# Relay.net
KiCad netlist of a schematic drawn in Altium Designer
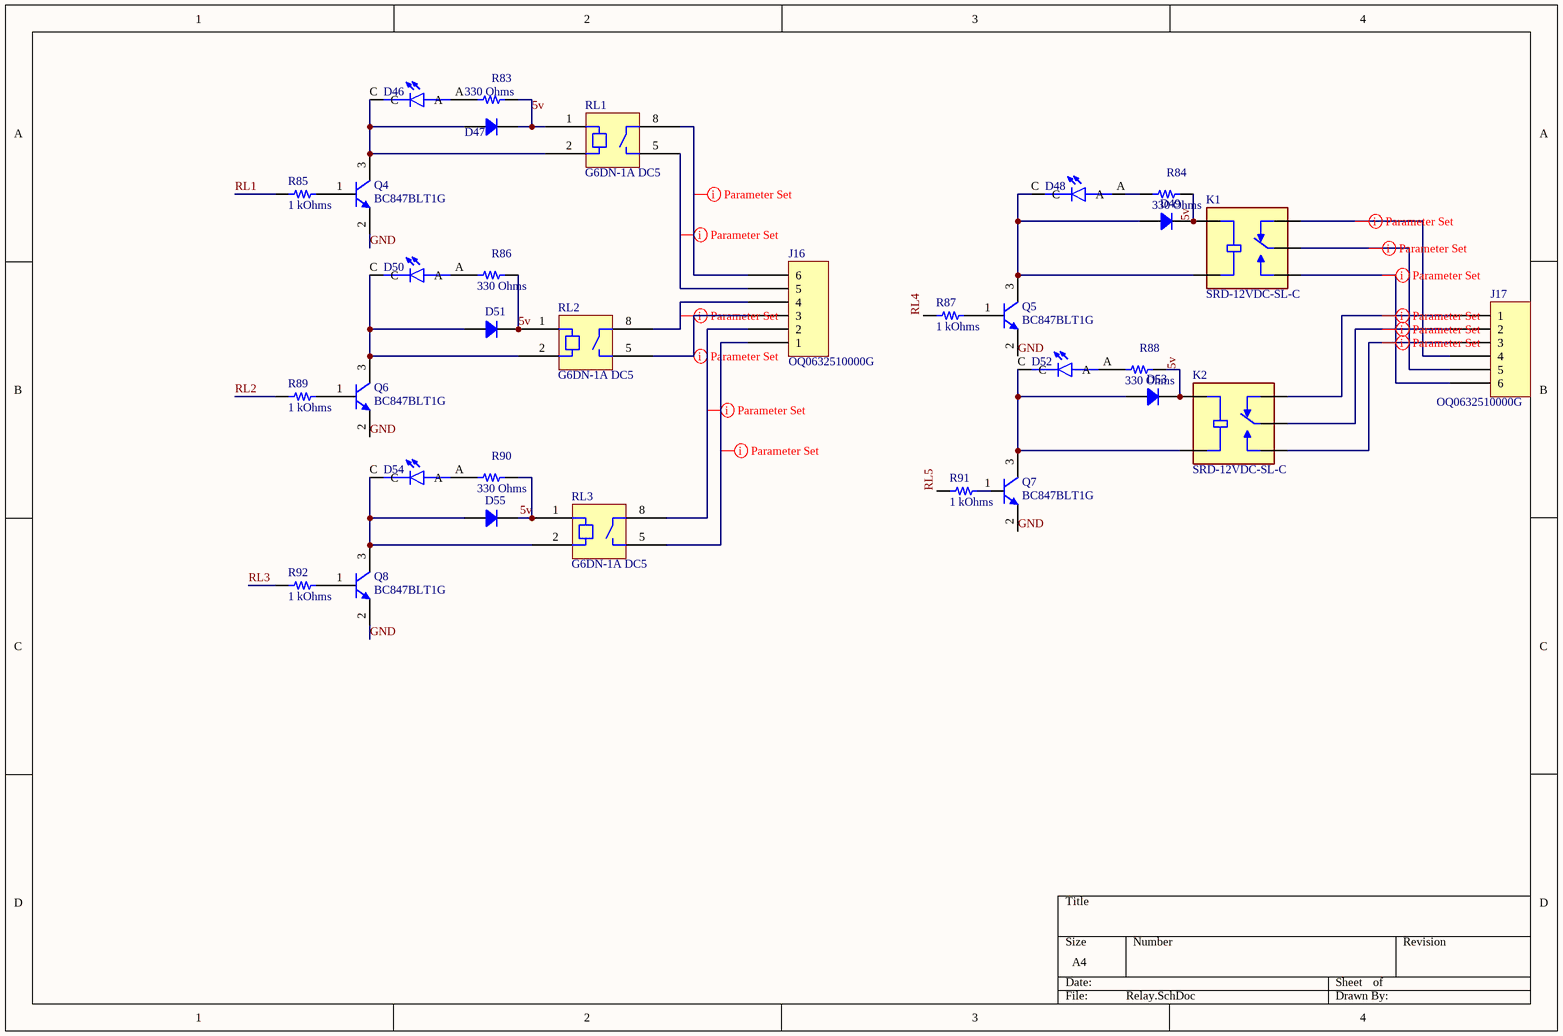
[diagram p0: Relay.SchDoc]

(export (version "E")
  (design (tool "Eeschema 10.0.6"))
  (components
    (comp (ref "D46")
      (value "597-3305-607F")
      (footprint "LEDC2012X70N")
      (description "LED Uni-Color Green 4-Pin Chip 0805 T/R")
      (libsource (lib "597-3305-607F") (part "597-3305-607F"))
    )
    (comp (ref "D47")
      (value "CGRA4007-G")
      (footprint "DO214AC SMA")
      (description "DIODE GEN PURP 1KV 1A DO214AC")
      (fields (field (name "MANUFACTURER") "Comchip Technology"))
      (libsource (lib "Celestial Altium Library - altium_library") (part "Diode"))
    )
    (comp (ref "D48")
      (value "597-3305-607F")
      (footprint "LEDC2012X70N")
      (description "LED Uni-Color Green 4-Pin Chip 0805 T/R")
      (libsource (lib "597-3305-607F") (part "597-3305-607F"))
    )
    (comp (ref "D49")
      (value "CGRA4007-G")
      (footprint "DO214AC SMA")
      (description "DIODE GEN PURP 1KV 1A DO214AC")
      (fields (field (name "MANUFACTURER") "Comchip Technology"))
      (libsource (lib "Celestial Altium Library - altium_library") (part "Diode"))
    )
    (comp (ref "D50")
      (value "597-3305-607F")
      (footprint "LEDC2012X70N")
      (description "LED Uni-Color Green 4-Pin Chip 0805 T/R")
      (libsource (lib "597-3305-607F") (part "597-3305-607F"))
    )
    (comp (ref "D51")
      (value "CGRA4007-G")
      (footprint "DO214AC SMA")
      (description "DIODE GEN PURP 1KV 1A DO214AC")
      (fields (field (name "MANUFACTURER") "Comchip Technology"))
      (libsource (lib "Celestial Altium Library - altium_library") (part "Diode"))
    )
    (comp (ref "D52")
      (value "597-3305-607F")
      (footprint "LEDC2012X70N")
      (description "LED Uni-Color Green 4-Pin Chip 0805 T/R")
      (libsource (lib "597-3305-607F") (part "597-3305-607F"))
    )
    (comp (ref "D53")
      (value "CGRA4007-G")
      (footprint "DO214AC SMA")
      (description "DIODE GEN PURP 1KV 1A DO214AC")
      (fields (field (name "MANUFACTURER") "Comchip Technology"))
      (libsource (lib "Celestial Altium Library - altium_library") (part "Diode"))
    )
    (comp (ref "D54")
      (value "597-3305-607F")
      (footprint "LEDC2012X70N")
      (description "LED Uni-Color Green 4-Pin Chip 0805 T/R")
      (libsource (lib "597-3305-607F") (part "597-3305-607F"))
    )
    (comp (ref "D55")
      (value "CGRA4007-G")
      (footprint "DO214AC SMA")
      (description "DIODE GEN PURP 1KV 1A DO214AC")
      (fields (field (name "MANUFACTURER") "Comchip Technology"))
      (libsource (lib "Celestial Altium Library - altium_library") (part "Diode"))
    )
    (comp (ref "J16")
      (value "OQ0632510000G")
      (footprint "FCI 06-381-6PIN")
      (description "TERM BLOCK HDR 6POS 90DEG 3.81MM")
      (fields (field (name "MANUFACTURER") "Amphenol Anytek"))
      (libsource (lib "") (part "6 Pin_1"))
    )
    (comp (ref "J17")
      (value "OQ0632510000G")
      (footprint "FCI 06-381-6PIN")
      (description "TERM BLOCK HDR 6POS 90DEG 3.81MM")
      (fields (field (name "MANUFACTURER") "Amphenol Anytek"))
      (libsource (lib "Celestial Altium Library - altium_library") (part "6 Pin"))
    )
    (comp (ref "K1")
      (value "SRD-12VDC-SL-C")
      (footprint "RELAY_SRD-12VDC-SL-C")
      (description "General Purpose Non Latching 12VDC SPDT Through Hole Relays RoHS")
      (fields (field (name "MF") "Songle Relay"))
      (libsource (lib "SRD-12VDC-SL-C") (part "SRD-12VDC-SL-C"))
    )
    (comp (ref "K2")
      (value "SRD-12VDC-SL-C")
      (footprint "RELAY_SRD-12VDC-SL-C")
      (description "General Purpose Non Latching 12VDC SPDT Through Hole Relays RoHS")
      (fields (field (name "MF") "Songle Relay"))
      (libsource (lib "SRD-12VDC-SL-C") (part "SRD-12VDC-SL-C"))
    )
    (comp (ref "Q4")
      (value "BC847BLT1G")
      (footprint "ON SEMI SOT-23-3")
      (description "TRANS NPN 45V 0.1A SOT23")
      (fields (field (name "MANUFACTURER") "ON Semiconductor"))
      (libsource (lib "Celestial Altium Library - altium_library") (part "ON SEMI NPN SOT-23-3"))
    )
    (comp (ref "Q5")
      (value "BC847BLT1G")
      (footprint "ON SEMI SOT-23-3")
      (description "TRANS NPN 45V 0.1A SOT23")
      (fields (field (name "MANUFACTURER") "ON Semiconductor"))
      (libsource (lib "Celestial Altium Library - altium_library") (part "ON SEMI NPN SOT-23-3"))
    )
    (comp (ref "Q6")
      (value "BC847BLT1G")
      (footprint "ON SEMI SOT-23-3")
      (description "TRANS NPN 45V 0.1A SOT23")
      (fields (field (name "MANUFACTURER") "ON Semiconductor"))
      (libsource (lib "Celestial Altium Library - altium_library") (part "ON SEMI NPN SOT-23-3"))
    )
    (comp (ref "Q7")
      (value "BC847BLT1G")
      (footprint "ON SEMI SOT-23-3")
      (description "TRANS NPN 45V 0.1A SOT23")
      (fields (field (name "MANUFACTURER") "ON Semiconductor"))
      (libsource (lib "Celestial Altium Library - altium_library") (part "ON SEMI NPN SOT-23-3"))
    )
    (comp (ref "Q8")
      (value "BC847BLT1G")
      (footprint "ON SEMI SOT-23-3")
      (description "TRANS NPN 45V 0.1A SOT23")
      (fields (field (name "MANUFACTURER") "ON Semiconductor"))
      (libsource (lib "Celestial Altium Library - altium_library") (part "ON SEMI NPN SOT-23-3"))
    )
    (comp (ref "R83")
      (value "330 Ohms")
      (footprint "RES 0805_2012")
      (description "RES SMD 330 OHM 1% 1/2W 0805")
      (fields (field (name "PART NUMBER") "CRCW0805330RFKEAHP") (field (name "MANUFACTURER") "Vishay Dale"))
      (libsource (lib "Celestial Altium Library - altium_library") (part "Resistor"))
    )
    (comp (ref "R84")
      (value "330 Ohms")
      (footprint "RES 0805_2012")
      (description "RES SMD 330 OHM 1% 1/2W 0805")
      (fields (field (name "PART NUMBER") "CRCW0805330RFKEAHP") (field (name "MANUFACTURER") "Vishay Dale"))
      (libsource (lib "Celestial Altium Library - altium_library") (part "Resistor"))
    )
    (comp (ref "R85")
      (value "1 kOhms")
      (footprint "RES 0805_2012")
      (description "RES SMD 1K OHM 1% 0.4W 0805")
      (fields (field (name "PART NUMBER") "ESR10EZPF1001") (field (name "MANUFACTURER") "Rohm Semiconductor"))
      (libsource (lib "Celestial Altium Library - altium_library") (part "Resistor"))
    )
    (comp (ref "R86")
      (value "330 Ohms")
      (footprint "RES 0805_2012")
      (description "RES SMD 330 OHM 1% 1/2W 0805")
      (fields (field (name "PART NUMBER") "CRCW0805330RFKEAHP") (field (name "MANUFACTURER") "Vishay Dale"))
      (libsource (lib "Celestial Altium Library - altium_library") (part "Resistor"))
    )
    (comp (ref "R87")
      (value "1 kOhms")
      (footprint "RES 0805_2012")
      (description "RES SMD 1K OHM 1% 0.4W 0805")
      (fields (field (name "PART NUMBER") "ESR10EZPF1001") (field (name "MANUFACTURER") "Rohm Semiconductor"))
      (libsource (lib "Celestial Altium Library - altium_library") (part "Resistor"))
    )
    (comp (ref "R88")
      (value "330 Ohms")
      (footprint "RES 0805_2012")
      (description "RES SMD 330 OHM 1% 1/2W 0805")
      (fields (field (name "PART NUMBER") "CRCW0805330RFKEAHP") (field (name "MANUFACTURER") "Vishay Dale"))
      (libsource (lib "Celestial Altium Library - altium_library") (part "Resistor"))
    )
    (comp (ref "R89")
      (value "1 kOhms")
      (footprint "RES 0805_2012")
      (description "RES SMD 1K OHM 1% 0.4W 0805")
      (fields (field (name "PART NUMBER") "ESR10EZPF1001") (field (name "MANUFACTURER") "Rohm Semiconductor"))
      (libsource (lib "Celestial Altium Library - altium_library") (part "Resistor"))
    )
    (comp (ref "R90")
      (value "330 Ohms")
      (footprint "RES 0805_2012")
      (description "RES SMD 330 OHM 1% 1/2W 0805")
      (fields (field (name "PART NUMBER") "CRCW0805330RFKEAHP") (field (name "MANUFACTURER") "Vishay Dale"))
      (libsource (lib "Celestial Altium Library - altium_library") (part "Resistor"))
    )
    (comp (ref "R91")
      (value "1 kOhms")
      (footprint "RES 0805_2012")
      (description "RES SMD 1K OHM 1% 0.4W 0805")
      (fields (field (name "PART NUMBER") "ESR10EZPF1001") (field (name "MANUFACTURER") "Rohm Semiconductor"))
      (libsource (lib "Celestial Altium Library - altium_library") (part "Resistor"))
    )
    (comp (ref "R92")
      (value "1 kOhms")
      (footprint "RES 0805_2012")
      (description "RES SMD 1K OHM 1% 0.4W 0805")
      (fields (field (name "PART NUMBER") "ESR10EZPF1001") (field (name "MANUFACTURER") "Rohm Semiconductor"))
      (libsource (lib "Celestial Altium Library - altium_library") (part "Resistor"))
    )
    (comp (ref "RL1")
      (value "G6DN-1A DC5")
      (footprint "OMRON G6DN")
      (description "RELAY GEN PURPOSE SPST 5A 5V")
      (fields (field (name "MANUFACTURER") "Omron Electronics Inc-EMC Div"))
      (libsource (lib "Celestial Altium Library - altium_library") (part "OMRON G6DN"))
    )
    (comp (ref "RL2")
      (value "G6DN-1A DC5")
      (footprint "OMRON G6DN")
      (description "RELAY GEN PURPOSE SPST 5A 5V")
      (fields (field (name "MANUFACTURER") "Omron Electronics Inc-EMC Div"))
      (libsource (lib "Celestial Altium Library - altium_library") (part "OMRON G6DN"))
    )
    (comp (ref "RL3")
      (value "G6DN-1A DC5")
      (footprint "OMRON G6DN")
      (description "RELAY GEN PURPOSE SPST 5A 5V")
      (fields (field (name "MANUFACTURER") "Omron Electronics Inc-EMC Div"))
      (libsource (lib "Celestial Altium Library - altium_library") (part "OMRON G6DN"))
    )
  )
  (nets
    (net (code "1") (name "/5v") (class "Default")
      (node (ref "D47") (pin "2") (pinfunction "2_2") (pintype "passive"))
      (node (ref "D49") (pin "2") (pinfunction "2_2") (pintype "passive"))
      (node (ref "D51") (pin "2") (pinfunction "2_2") (pintype "passive"))
      (node (ref "D53") (pin "2") (pinfunction "2_2") (pintype "passive"))
      (node (ref "D55") (pin "2") (pinfunction "2_2") (pintype "passive"))
      (node (ref "K1") (pin "COIL1") (pinfunction "COIL1_COIL1") (pintype "passive"))
      (node (ref "K2") (pin "COIL1") (pinfunction "COIL1_COIL1") (pintype "passive"))
      (node (ref "R83") (pin "2") (pinfunction "2_2") (pintype "passive"))
      (node (ref "R84") (pin "2") (pinfunction "2_2") (pintype "passive"))
      (node (ref "R86") (pin "2") (pinfunction "2_2") (pintype "passive"))
      (node (ref "R88") (pin "2") (pinfunction "2_2") (pintype "passive"))
      (node (ref "R90") (pin "2") (pinfunction "2_2") (pintype "passive"))
      (node (ref "RL1") (pin "1") (pinfunction "COIL1_1") (pintype "passive"))
      (node (ref "RL2") (pin "1") (pinfunction "COIL1_1") (pintype "passive"))
      (node (ref "RL3") (pin "1") (pinfunction "COIL1_1") (pintype "passive"))
    )
    (net (code "2") (name "/GND") (class "Default")
      (node (ref "Q4") (pin "2") (pinfunction "E_2") (pintype "passive"))
      (node (ref "Q5") (pin "2") (pinfunction "E_2") (pintype "passive"))
      (node (ref "Q6") (pin "2") (pinfunction "E_2") (pintype "passive"))
      (node (ref "Q7") (pin "2") (pinfunction "E_2") (pintype "passive"))
      (node (ref "Q8") (pin "2") (pinfunction "E_2") (pintype "passive"))
    )
    (net (code "3") (name "/RL1") (class "Default")
      (node (ref "R85") (pin "1") (pinfunction "1_1") (pintype "passive"))
    )
    (net (code "4") (name "/RL2") (class "Default")
      (node (ref "R89") (pin "1") (pinfunction "1_1") (pintype "passive"))
    )
    (net (code "5") (name "/RL3") (class "Default")
      (node (ref "R92") (pin "1") (pinfunction "1_1") (pintype "passive"))
    )
    (net (code "6") (name "/RL4") (class "Default")
      (node (ref "R87") (pin "1") (pinfunction "1_1") (pintype "passive"))
    )
    (net (code "7") (name "/RL5") (class "Default")
      (node (ref "R91") (pin "1") (pinfunction "1_1") (pintype "passive"))
    )
    (net (code "8") (name "Net-(D46-PadA)") (class "Default")
      (node (ref "D46") (pin "A") (pinfunction "A_A") (pintype "passive"))
      (node (ref "R83") (pin "1") (pinfunction "1_1") (pintype "passive"))
    )
    (net (code "9") (name "Net-(D48-PadA)") (class "Default")
      (node (ref "D48") (pin "A") (pinfunction "A_A") (pintype "passive"))
      (node (ref "R84") (pin "1") (pinfunction "1_1") (pintype "passive"))
    )
    (net (code "10") (name "Net-(D50-PadA)") (class "Default")
      (node (ref "D50") (pin "A") (pinfunction "A_A") (pintype "passive"))
      (node (ref "R86") (pin "1") (pinfunction "1_1") (pintype "passive"))
    )
    (net (code "11") (name "Net-(D52-PadA)") (class "Default")
      (node (ref "D52") (pin "A") (pinfunction "A_A") (pintype "passive"))
      (node (ref "R88") (pin "1") (pinfunction "1_1") (pintype "passive"))
    )
    (net (code "12") (name "Net-(D54-PadA)") (class "Default")
      (node (ref "D54") (pin "A") (pinfunction "A_A") (pintype "passive"))
      (node (ref "R90") (pin "1") (pinfunction "1_1") (pintype "passive"))
    )
    (net (code "13") (name "Net-(J17-Pad1)") (class "Default")
      (node (ref "J17") (pin "1") (pinfunction "1_1") (pintype "passive"))
      (node (ref "K2") (pin "NC") (pinfunction "NC_NC") (pintype "passive"))
    )
    (net (code "14") (name "Net-(J17-Pad2)") (class "Default")
      (node (ref "J17") (pin "2") (pinfunction "2_2") (pintype "passive"))
      (node (ref "K2") (pin "COM") (pinfunction "COM_COM") (pintype "passive"))
    )
    (net (code "15") (name "Net-(J17-Pad3)") (class "Default")
      (node (ref "J17") (pin "3") (pinfunction "3_3") (pintype "passive"))
      (node (ref "K2") (pin "NO") (pinfunction "NO_NO") (pintype "passive"))
    )
    (net (code "16") (name "Net-(J17-Pad4)") (class "Default")
      (node (ref "J17") (pin "4") (pinfunction "4_4") (pintype "passive"))
      (node (ref "K1") (pin "NC") (pinfunction "NC_NC") (pintype "passive"))
    )
    (net (code "17") (name "Net-(J17-Pad5)") (class "Default")
      (node (ref "J17") (pin "5") (pinfunction "5_5") (pintype "passive"))
      (node (ref "K1") (pin "COM") (pinfunction "COM_COM") (pintype "passive"))
    )
    (net (code "18") (name "Net-(J17-Pad6)") (class "Default")
      (node (ref "J17") (pin "6") (pinfunction "6_6") (pintype "passive"))
      (node (ref "K1") (pin "NO") (pinfunction "NO_NO") (pintype "passive"))
    )
    (net (code "19") (name "Net-(Q4-B)") (class "Default")
      (node (ref "Q4") (pin "1") (pinfunction "B_1") (pintype "passive"))
      (node (ref "R85") (pin "2") (pinfunction "2_2") (pintype "passive"))
    )
    (net (code "20") (name "Net-(Q4-C)") (class "Default")
      (node (ref "D46") (pin "C") (pinfunction "C_C") (pintype "passive"))
      (node (ref "D47") (pin "1") (pinfunction "1_1") (pintype "passive"))
      (node (ref "Q4") (pin "3") (pinfunction "C_3") (pintype "passive"))
      (node (ref "RL1") (pin "2") (pinfunction "COIL2_2") (pintype "passive"))
    )
    (net (code "21") (name "Net-(Q5-B)") (class "Default")
      (node (ref "Q5") (pin "1") (pinfunction "B_1") (pintype "passive"))
      (node (ref "R87") (pin "2") (pinfunction "2_2") (pintype "passive"))
    )
    (net (code "22") (name "Net-(Q5-C)") (class "Default")
      (node (ref "D48") (pin "C") (pinfunction "C_C") (pintype "passive"))
      (node (ref "D49") (pin "1") (pinfunction "1_1") (pintype "passive"))
      (node (ref "K1") (pin "COIL2") (pinfunction "COIL2_COIL2") (pintype "passive"))
      (node (ref "Q5") (pin "3") (pinfunction "C_3") (pintype "passive"))
    )
    (net (code "23") (name "Net-(Q6-B)") (class "Default")
      (node (ref "Q6") (pin "1") (pinfunction "B_1") (pintype "passive"))
      (node (ref "R89") (pin "2") (pinfunction "2_2") (pintype "passive"))
    )
    (net (code "24") (name "Net-(Q6-C)") (class "Default")
      (node (ref "D50") (pin "C") (pinfunction "C_C") (pintype "passive"))
      (node (ref "D51") (pin "1") (pinfunction "1_1") (pintype "passive"))
      (node (ref "Q6") (pin "3") (pinfunction "C_3") (pintype "passive"))
      (node (ref "RL2") (pin "2") (pinfunction "COIL2_2") (pintype "passive"))
    )
    (net (code "25") (name "Net-(Q7-B)") (class "Default")
      (node (ref "Q7") (pin "1") (pinfunction "B_1") (pintype "passive"))
      (node (ref "R91") (pin "2") (pinfunction "2_2") (pintype "passive"))
    )
    (net (code "26") (name "Net-(Q7-C)") (class "Default")
      (node (ref "D52") (pin "C") (pinfunction "C_C") (pintype "passive"))
      (node (ref "D53") (pin "1") (pinfunction "1_1") (pintype "passive"))
      (node (ref "K2") (pin "COIL2") (pinfunction "COIL2_COIL2") (pintype "passive"))
      (node (ref "Q7") (pin "3") (pinfunction "C_3") (pintype "passive"))
    )
    (net (code "27") (name "Net-(Q8-B)") (class "Default")
      (node (ref "Q8") (pin "1") (pinfunction "B_1") (pintype "passive"))
      (node (ref "R92") (pin "2") (pinfunction "2_2") (pintype "passive"))
    )
    (net (code "28") (name "Net-(Q8-C)") (class "Default")
      (node (ref "D54") (pin "C") (pinfunction "C_C") (pintype "passive"))
      (node (ref "D55") (pin "1") (pinfunction "1_1") (pintype "passive"))
      (node (ref "Q8") (pin "3") (pinfunction "C_3") (pintype "passive"))
      (node (ref "RL3") (pin "2") (pinfunction "COIL2_2") (pintype "passive"))
    )
    (net (code "29") (name "Net-(RL1-TERM1)") (class "Default")
      (node (ref "J16") (pin "5") (pinfunction "5_5") (pintype "passive"))
      (node (ref "RL1") (pin "5") (pinfunction "TERM1_5") (pintype "passive"))
    )
    (net (code "30") (name "Net-(RL1-TERM2)") (class "Default")
      (node (ref "J16") (pin "6") (pinfunction "6_6") (pintype "passive"))
      (node (ref "RL1") (pin "8") (pinfunction "TERM2_8") (pintype "passive"))
    )
    (net (code "31") (name "Net-(RL2-TERM1)") (class "Default")
      (node (ref "J16") (pin "3") (pinfunction "3_3") (pintype "passive"))
      (node (ref "RL2") (pin "5") (pinfunction "TERM1_5") (pintype "passive"))
    )
    (net (code "32") (name "Net-(RL2-TERM2)") (class "Default")
      (node (ref "J16") (pin "4") (pinfunction "4_4") (pintype "passive"))
      (node (ref "RL2") (pin "8") (pinfunction "TERM2_8") (pintype "passive"))
    )
    (net (code "33") (name "Net-(RL3-TERM1)") (class "Default")
      (node (ref "J16") (pin "1") (pinfunction "1_1") (pintype "passive"))
      (node (ref "RL3") (pin "5") (pinfunction "TERM1_5") (pintype "passive"))
    )
    (net (code "34") (name "Net-(RL3-TERM2)") (class "Default")
      (node (ref "J16") (pin "2") (pinfunction "2_2") (pintype "passive"))
      (node (ref "RL3") (pin "8") (pinfunction "TERM2_8") (pintype "passive"))
    )
  )
)
